# R3D2_v2.net
KiCad netlist of a schematic drawn in EAGLE
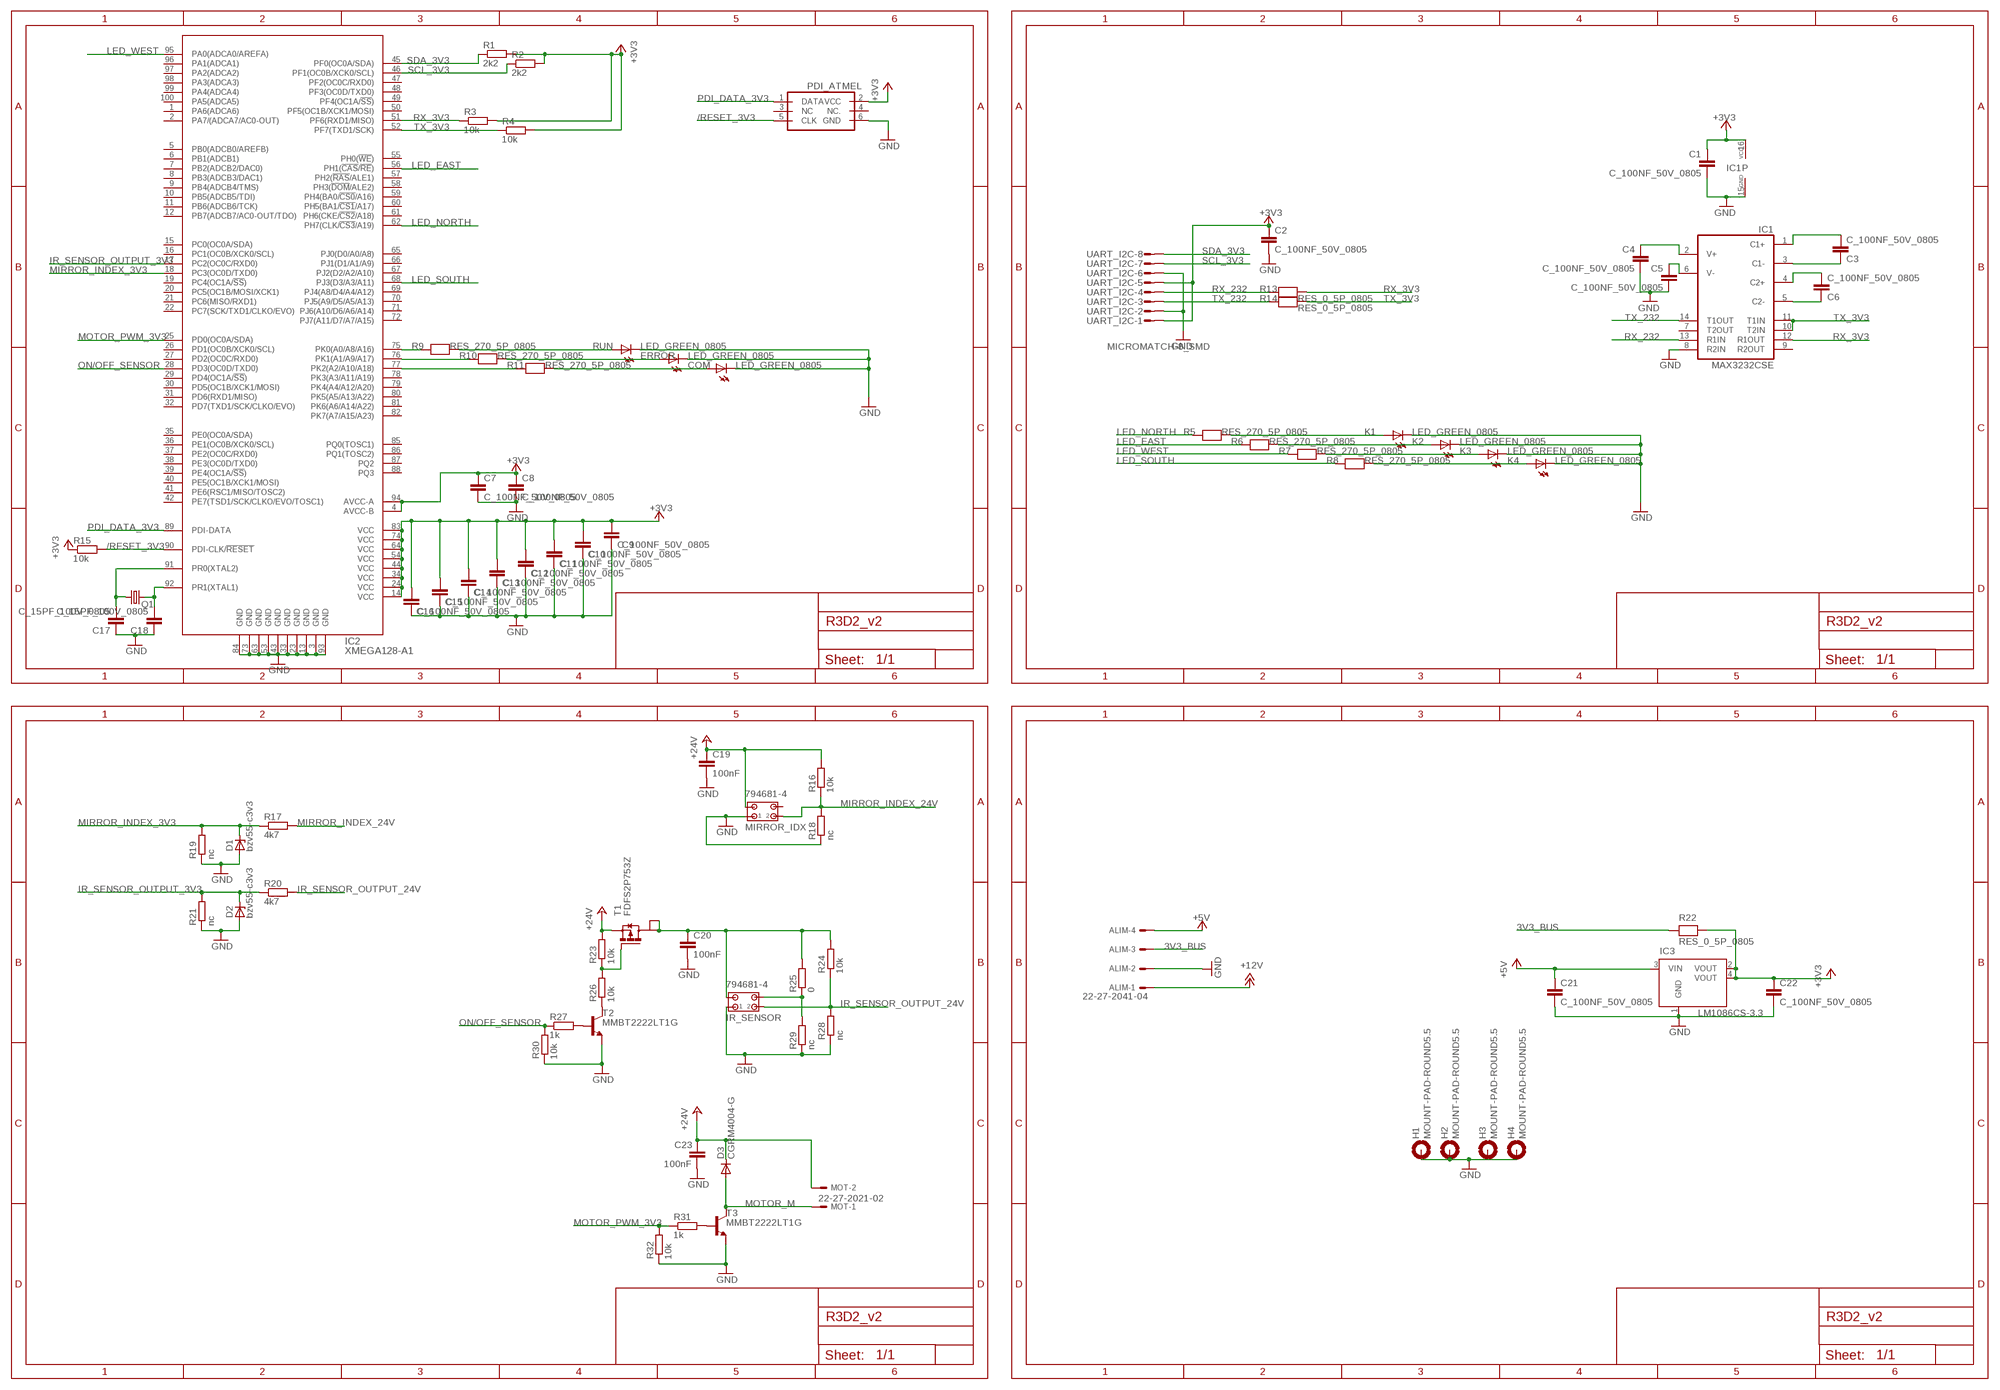
[diagram p0: schematic, sheet 1]

(export (version "E")
  (design (tool "Eeschema 10.0.6"))
  (components
    (comp (ref "ALIM")
      (value "22-27-2041-04")
      (footprint "eagle-import:6410-04")
      (libsource (lib "eagle-import") (part "22-?-0427-2041"))
    )
    (comp (ref "C1")
      (value "C_100NF_50V_0805")
      (footprint "eagle-import:C0805")
      (libsource (lib "eagle-import") (part "C_100NF_50V_0805"))
    )
    (comp (ref "C2")
      (value "C_100NF_50V_0805")
      (footprint "eagle-import:C0805")
      (libsource (lib "eagle-import") (part "C_100NF_50V_0805"))
    )
    (comp (ref "C3")
      (value "C_100NF_50V_0805")
      (footprint "eagle-import:C0805")
      (libsource (lib "eagle-import") (part "C_100NF_50V_0805"))
    )
    (comp (ref "C4")
      (value "C_100NF_50V_0805")
      (footprint "eagle-import:C0805")
      (libsource (lib "eagle-import") (part "C_100NF_50V_0805"))
    )
    (comp (ref "C5")
      (value "C_100NF_50V_0805")
      (footprint "eagle-import:C0805")
      (libsource (lib "eagle-import") (part "C_100NF_50V_0805"))
    )
    (comp (ref "C6")
      (value "C_100NF_50V_0805")
      (footprint "eagle-import:C0805")
      (libsource (lib "eagle-import") (part "C_100NF_50V_0805"))
    )
    (comp (ref "C7")
      (value "C_100NF_50V_0805")
      (footprint "eagle-import:C0805")
      (libsource (lib "eagle-import") (part "C_100NF_50V_0805"))
    )
    (comp (ref "C8")
      (value "C_100NF_50V_0805")
      (footprint "eagle-import:C0805")
      (libsource (lib "eagle-import") (part "C_100NF_50V_0805"))
    )
    (comp (ref "C9")
      (value "C_100NF_50V_0805")
      (footprint "eagle-import:C0805")
      (libsource (lib "eagle-import") (part "C_100NF_50V_0805"))
    )
    (comp (ref "C10")
      (value "C_100NF_50V_0805")
      (footprint "eagle-import:C0805")
      (libsource (lib "eagle-import") (part "C_100NF_50V_0805"))
    )
    (comp (ref "C11")
      (value "C_100NF_50V_0805")
      (footprint "eagle-import:C0805")
      (libsource (lib "eagle-import") (part "C_100NF_50V_0805"))
    )
    (comp (ref "C12")
      (value "C_100NF_50V_0805")
      (footprint "eagle-import:C0805")
      (libsource (lib "eagle-import") (part "C_100NF_50V_0805"))
    )
    (comp (ref "C13")
      (value "C_100NF_50V_0805")
      (footprint "eagle-import:C0805")
      (libsource (lib "eagle-import") (part "C_100NF_50V_0805"))
    )
    (comp (ref "C14")
      (value "C_100NF_50V_0805")
      (footprint "eagle-import:C0805")
      (libsource (lib "eagle-import") (part "C_100NF_50V_0805"))
    )
    (comp (ref "C15")
      (value "C_100NF_50V_0805")
      (footprint "eagle-import:C0805")
      (libsource (lib "eagle-import") (part "C_100NF_50V_0805"))
    )
    (comp (ref "C16")
      (value "C_100NF_50V_0805")
      (footprint "eagle-import:C0805")
      (libsource (lib "eagle-import") (part "C_100NF_50V_0805"))
    )
    (comp (ref "C17")
      (value "C_15PF_100V_0805")
      (footprint "eagle-import:C0805")
      (libsource (lib "eagle-import") (part "C_15PF_100V_0805"))
    )
    (comp (ref "C18")
      (value "C_15PF_100V_0805")
      (footprint "eagle-import:C0805")
      (libsource (lib "eagle-import") (part "C_15PF_100V_0805"))
    )
    (comp (ref "C19")
      (value "100nF")
      (footprint "eagle-import:C0805")
      (libsource (lib "eagle-import") (part "C-EUC0805"))
    )
    (comp (ref "C20")
      (value "100nF")
      (footprint "eagle-import:C0603")
      (libsource (lib "eagle-import") (part "C-EUC0603"))
    )
    (comp (ref "C21")
      (value "C_100NF_50V_0805")
      (footprint "eagle-import:C0805")
      (libsource (lib "eagle-import") (part "C_100NF_50V_0805"))
    )
    (comp (ref "C22")
      (value "C_100NF_50V_0805")
      (footprint "eagle-import:C0805")
      (libsource (lib "eagle-import") (part "C_100NF_50V_0805"))
    )
    (comp (ref "C23")
      (value "100nF")
      (footprint "eagle-import:C0805")
      (libsource (lib "eagle-import") (part "C-EUC0805"))
    )
    (comp (ref "COM")
      (value "LED_GREEN_0805")
      (footprint "eagle-import:CHIP-LED0805")
      (libsource (lib "eagle-import") (part "LED_GREEN_0805"))
    )
    (comp (ref "D1")
      (value "bzv55-c3v3")
      (footprint "eagle-import:SOD80C")
      (libsource (lib "eagle-import") (part "ZENER-DIODESOD80C"))
    )
    (comp (ref "D2")
      (value "bzv55-c3v3")
      (footprint "eagle-import:SOD80C")
      (libsource (lib "eagle-import") (part "ZENER-DIODESOD80C"))
    )
    (comp (ref "D3")
      (value "CGRM4004-G")
      (footprint "eagle-import:SOD-123_MINI-SMA")
      (libsource (lib "eagle-import") (part "CGRM400-G4"))
    )
    (comp (ref "ERROR")
      (value "LED_GREEN_0805")
      (footprint "eagle-import:CHIP-LED0805")
      (libsource (lib "eagle-import") (part "LED_GREEN_0805"))
    )
    (comp (ref "H1")
      (value "MOUNT-PAD-ROUND5.5")
      (footprint "eagle-import:5,5-PAD")
      (libsource (lib "eagle-import") (part "MOUNT-PAD-ROUND5.5"))
    )
    (comp (ref "H2")
      (value "MOUNT-PAD-ROUND5.5")
      (footprint "eagle-import:5,5-PAD")
      (libsource (lib "eagle-import") (part "MOUNT-PAD-ROUND5.5"))
    )
    (comp (ref "H3")
      (value "MOUNT-PAD-ROUND5.5")
      (footprint "eagle-import:5,5-PAD")
      (libsource (lib "eagle-import") (part "MOUNT-PAD-ROUND5.5"))
    )
    (comp (ref "H4")
      (value "MOUNT-PAD-ROUND5.5")
      (footprint "eagle-import:5,5-PAD")
      (libsource (lib "eagle-import") (part "MOUNT-PAD-ROUND5.5"))
    )
    (comp (ref "IC1")
      (value "MAX3232CSE")
      (footprint "eagle-import:SO16")
      (libsource (lib "eagle-import") (part "MAX3232SEC"))
    )
    (comp (ref "IC2")
      (value "XMEGA128-A1")
      (footprint "eagle-import:TQFP100")
      (libsource (lib "eagle-import") (part "XMEGA-A1TQFP"))
    )
    (comp (ref "IC3")
      (value "LM1086CS-3.3")
      (footprint "eagle-import:TO263")
      (libsource (lib "eagle-import") (part "LM1086CS-3.3"))
    )
    (comp (ref "IR_SENSOR")
      (value "794681-4")
      (footprint "eagle-import:794681-4")
      (libsource (lib "eagle-import") (part "794681-4"))
    )
    (comp (ref "K1")
      (value "LED_GREEN_0805")
      (footprint "eagle-import:CHIP-LED0805")
      (libsource (lib "eagle-import") (part "LED_GREEN_0805"))
    )
    (comp (ref "K2")
      (value "LED_GREEN_0805")
      (footprint "eagle-import:CHIP-LED0805")
      (libsource (lib "eagle-import") (part "LED_GREEN_0805"))
    )
    (comp (ref "K3")
      (value "LED_GREEN_0805")
      (footprint "eagle-import:CHIP-LED0805")
      (libsource (lib "eagle-import") (part "LED_GREEN_0805"))
    )
    (comp (ref "K4")
      (value "LED_GREEN_0805")
      (footprint "eagle-import:CHIP-LED0805")
      (libsource (lib "eagle-import") (part "LED_GREEN_0805"))
    )
    (comp (ref "MIRROR_IDX")
      (value "794681-4")
      (footprint "eagle-import:794681-4")
      (libsource (lib "eagle-import") (part "794681-4"))
    )
    (comp (ref "MOT")
      (value "22-27-2021-02")
      (footprint "eagle-import:6410-02")
      (libsource (lib "eagle-import") (part "22-?-0227-2021"))
    )
    (comp (ref "PDI_ATMEL")
      (value "PDI_ATMEL")
      (footprint "eagle-import:ML6")
      (libsource (lib "eagle-import") (part "PDI_ATMEL"))
    )
    (comp (ref "Q1")
      (value "CRYSTAL_16MHZ_HC49UP")
      (footprint "eagle-import:HC49UP")
      (libsource (lib "eagle-import") (part "CRYSTAL_16MHZ_HC49UP"))
    )
    (comp (ref "R1")
      (value "2k2")
      (footprint "eagle-import:R0603")
      (libsource (lib "eagle-import") (part "R-EU_R0603"))
    )
    (comp (ref "R2")
      (value "2k2")
      (footprint "eagle-import:R0603")
      (libsource (lib "eagle-import") (part "R-EU_R0603"))
    )
    (comp (ref "R3")
      (value "10k")
      (footprint "eagle-import:R0603")
      (libsource (lib "eagle-import") (part "R-EU_R0603"))
    )
    (comp (ref "R4")
      (value "10k")
      (footprint "eagle-import:R0603")
      (libsource (lib "eagle-import") (part "R-EU_R0603"))
    )
    (comp (ref "R5")
      (value "RES_270_5P_0805")
      (footprint "eagle-import:R0805")
      (libsource (lib "eagle-import") (part "RES_270_5P_0805"))
    )
    (comp (ref "R6")
      (value "RES_270_5P_0805")
      (footprint "eagle-import:R0805")
      (libsource (lib "eagle-import") (part "RES_270_5P_0805"))
    )
    (comp (ref "R7")
      (value "RES_270_5P_0805")
      (footprint "eagle-import:R0805")
      (libsource (lib "eagle-import") (part "RES_270_5P_0805"))
    )
    (comp (ref "R8")
      (value "RES_270_5P_0805")
      (footprint "eagle-import:R0805")
      (libsource (lib "eagle-import") (part "RES_270_5P_0805"))
    )
    (comp (ref "R9")
      (value "RES_270_5P_0805")
      (footprint "eagle-import:R0805")
      (libsource (lib "eagle-import") (part "RES_270_5P_0805"))
    )
    (comp (ref "R10")
      (value "RES_270_5P_0805")
      (footprint "eagle-import:R0805")
      (libsource (lib "eagle-import") (part "RES_270_5P_0805"))
    )
    (comp (ref "R11")
      (value "RES_270_5P_0805")
      (footprint "eagle-import:R0805")
      (libsource (lib "eagle-import") (part "RES_270_5P_0805"))
    )
    (comp (ref "R13")
      (value "RES_0_5P_0805")
      (footprint "eagle-import:R0805")
      (libsource (lib "eagle-import") (part "RES_0_5P_0805"))
    )
    (comp (ref "R14")
      (value "RES_0_5P_0805")
      (footprint "eagle-import:R0805")
      (libsource (lib "eagle-import") (part "RES_0_5P_0805"))
    )
    (comp (ref "R15")
      (value "10k")
      (footprint "eagle-import:R0603")
      (libsource (lib "eagle-import") (part "R-EU_R0603"))
    )
    (comp (ref "R16")
      (value "10k")
      (footprint "eagle-import:R0603")
      (libsource (lib "eagle-import") (part "R-EU_R0603"))
    )
    (comp (ref "R17")
      (value "4k7")
      (footprint "eagle-import:R0805")
      (libsource (lib "eagle-import") (part "R-EU_R0805"))
    )
    (comp (ref "R18")
      (value "nc")
      (footprint "eagle-import:R0805")
      (libsource (lib "eagle-import") (part "R-EU_R0805"))
    )
    (comp (ref "R19")
      (value "nc")
      (footprint "eagle-import:R0603")
      (libsource (lib "eagle-import") (part "R-EU_R0603"))
    )
    (comp (ref "R20")
      (value "4k7")
      (footprint "eagle-import:R0805")
      (libsource (lib "eagle-import") (part "R-EU_R0805"))
    )
    (comp (ref "R21")
      (value "nc")
      (footprint "eagle-import:R0603")
      (libsource (lib "eagle-import") (part "R-EU_R0603"))
    )
    (comp (ref "R22")
      (value "RES_0_5P_0805")
      (footprint "eagle-import:R0805")
      (libsource (lib "eagle-import") (part "RES_0_5P_0805"))
    )
    (comp (ref "R23")
      (value "10k")
      (footprint "eagle-import:R0603")
      (libsource (lib "eagle-import") (part "R-EU_R0603"))
    )
    (comp (ref "R24")
      (value "10k")
      (footprint "eagle-import:R0603")
      (libsource (lib "eagle-import") (part "R-EU_R0603"))
    )
    (comp (ref "R25")
      (value "0")
      (footprint "eagle-import:R0603")
      (libsource (lib "eagle-import") (part "R-EU_R0603"))
    )
    (comp (ref "R26")
      (value "10k")
      (footprint "eagle-import:R0603")
      (libsource (lib "eagle-import") (part "R-EU_R0603"))
    )
    (comp (ref "R27")
      (value "1k")
      (footprint "eagle-import:R0603")
      (libsource (lib "eagle-import") (part "R-EU_R0603"))
    )
    (comp (ref "R28")
      (value "nc")
      (footprint "eagle-import:R0603")
      (libsource (lib "eagle-import") (part "R-EU_R0603"))
    )
    (comp (ref "R29")
      (value "nc")
      (footprint "eagle-import:R0603")
      (libsource (lib "eagle-import") (part "R-EU_R0603"))
    )
    (comp (ref "R30")
      (value "10k")
      (footprint "eagle-import:R0603")
      (libsource (lib "eagle-import") (part "R-EU_R0603"))
    )
    (comp (ref "R31")
      (value "1k")
      (footprint "eagle-import:R0603")
      (libsource (lib "eagle-import") (part "R-EU_R0603"))
    )
    (comp (ref "R32")
      (value "10k")
      (footprint "eagle-import:R0603")
      (libsource (lib "eagle-import") (part "R-EU_R0603"))
    )
    (comp (ref "RUN")
      (value "LED_GREEN_0805")
      (footprint "eagle-import:CHIP-LED0805")
      (libsource (lib "eagle-import") (part "LED_GREEN_0805"))
    )
    (comp (ref "T1")
      (value "FDFS2P753Z")
      (footprint "eagle-import:SO8")
      (libsource (lib "eagle-import") (part "FDFS2P753Z"))
    )
    (comp (ref "T2")
      (value "MMBT2222LT1G")
      (footprint "eagle-import:SOT23-BEC")
      (libsource (lib "eagle-import") (part "-NPN-SOT23-BECMMBT2222ALT1"))
    )
    (comp (ref "T3")
      (value "MMBT2222LT1G")
      (footprint "eagle-import:SOT23-BEC")
      (libsource (lib "eagle-import") (part "-NPN-SOT23-BECMMBT2222ALT1"))
    )
    (comp (ref "UART_I2C")
      (value "MICROMATCH-8_SMD")
      (footprint "eagle-import:MICROMATCH-8_SMD")
      (libsource (lib "eagle-import") (part "MICROMATCH-8_SMD"))
    )
  )
  (nets
    (net (code "1") (name "+3V3") (class "Default")
      (node (ref "C1") (pin "1") (pinfunction "1_1") (pintype "passive"))
      (node (ref "C10") (pin "1") (pinfunction "1_1") (pintype "passive"))
      (node (ref "C11") (pin "1") (pinfunction "1_1") (pintype "passive"))
      (node (ref "C12") (pin "1") (pinfunction "1_1") (pintype "passive"))
      (node (ref "C13") (pin "1") (pinfunction "1_1") (pintype "passive"))
      (node (ref "C14") (pin "1") (pinfunction "1_1") (pintype "passive"))
      (node (ref "C15") (pin "1") (pinfunction "1_1") (pintype "passive"))
      (node (ref "C16") (pin "1") (pinfunction "1_1") (pintype "passive"))
      (node (ref "C2") (pin "1") (pinfunction "1_1") (pintype "passive"))
      (node (ref "C22") (pin "1") (pinfunction "1_1") (pintype "passive"))
      (node (ref "C7") (pin "1") (pinfunction "1_1") (pintype "passive"))
      (node (ref "C8") (pin "1") (pinfunction "1_1") (pintype "passive"))
      (node (ref "C9") (pin "1") (pinfunction "1_1") (pintype "passive"))
      (node (ref "IC1") (pin "16") (pinfunction "VCC_16") (pintype "power_in"))
      (node (ref "IC2") (pin "14") (pinfunction "VCC_14") (pintype "power_in"))
      (node (ref "IC2") (pin "24") (pinfunction "VCC_24") (pintype "power_in"))
      (node (ref "IC2") (pin "34") (pinfunction "VCC_34") (pintype "power_in"))
      (node (ref "IC2") (pin "4") (pinfunction "AVCC-B_4") (pintype "power_in"))
      (node (ref "IC2") (pin "44") (pinfunction "VCC_44") (pintype "power_in"))
      (node (ref "IC2") (pin "54") (pinfunction "VCC_54") (pintype "power_in"))
      (node (ref "IC2") (pin "64") (pinfunction "VCC_64") (pintype "power_in"))
      (node (ref "IC2") (pin "74") (pinfunction "VCC_74") (pintype "power_in"))
      (node (ref "IC2") (pin "83") (pinfunction "VCC_83") (pintype "power_in"))
      (node (ref "IC2") (pin "94") (pinfunction "AVCC-A_94") (pintype "power_in"))
      (node (ref "IC3") (pin "2") (pinfunction "VOUT_2") (pintype "bidirectional"))
      (node (ref "IC3") (pin "4") (pinfunction "VOUT_4") (pintype "bidirectional"))
      (node (ref "PDI_ATMEL") (pin "2") (pinfunction "VCC_2") (pintype "passive"))
      (node (ref "R1") (pin "2") (pinfunction "2_2") (pintype "passive"))
      (node (ref "R15") (pin "1") (pinfunction "1_1") (pintype "passive"))
      (node (ref "R2") (pin "2") (pinfunction "2_2") (pintype "passive"))
      (node (ref "R22") (pin "2") (pinfunction "2_2") (pintype "bidirectional"))
      (node (ref "R3") (pin "2") (pinfunction "2_2") (pintype "passive"))
      (node (ref "R4") (pin "2") (pinfunction "2_2") (pintype "passive"))
      (node (ref "UART_I2C") (pin "1") (pinfunction "S_1") (pintype "passive"))
      (node (ref "UART_I2C") (pin "5") (pinfunction "S_5") (pintype "passive"))
    )
    (net (code "2") (name "+5V") (class "Default")
      (node (ref "ALIM") (pin "4") (pinfunction "S_4") (pintype "passive"))
      (node (ref "C21") (pin "1") (pinfunction "1_1") (pintype "passive"))
      (node (ref "IC3") (pin "3") (pinfunction "VIN_3") (pintype "bidirectional"))
    )
    (net (code "3") (name "+12V") (class "Default")
      (node (ref "ALIM") (pin "1") (pinfunction "S_1") (pintype "passive"))
    )
    (net (code "4") (name "+24V") (class "Default")
      (node (ref "C19") (pin "1") (pinfunction "1_1") (pintype "passive"))
      (node (ref "C23") (pin "1") (pinfunction "1_1") (pintype "passive"))
      (node (ref "D3") (pin "C") (pinfunction "C_C") (pintype "passive"))
      (node (ref "MIRROR_IDX") (pin "3") (pinfunction "3_3") (pintype "passive"))
      (node (ref "MOT") (pin "2") (pinfunction "S_2") (pintype "passive"))
      (node (ref "R16") (pin "2") (pinfunction "2_2") (pintype "passive"))
      (node (ref "R23") (pin "2") (pinfunction "2_2") (pintype "passive"))
      (node (ref "T1") (pin "3") (pinfunction "S_3") (pintype "passive"))
    )
    (net (code "5") (name "/3V3_BUS") (class "Default")
      (node (ref "ALIM") (pin "3") (pinfunction "S_3") (pintype "passive"))
      (node (ref "R22") (pin "1") (pinfunction "1_1") (pintype "bidirectional"))
    )
    (net (code "6") (name "/IR_SENSOR_OUTPUT_3V3") (class "Default")
      (node (ref "D2") (pin "C") (pinfunction "C_C") (pintype "passive"))
      (node (ref "IC2") (pin "17") (pinfunction "PC2(OC0C/RXD0)_17") (pintype "bidirectional"))
      (node (ref "R20") (pin "1") (pinfunction "1_1") (pintype "passive"))
      (node (ref "R21") (pin "2") (pinfunction "2_2") (pintype "passive"))
    )
    (net (code "7") (name "/IR_SENSOR_OUTPUT_24V") (class "Default")
      (node (ref "IR_SENSOR") (pin "2") (pinfunction "2_2") (pintype "passive"))
      (node (ref "R20") (pin "2") (pinfunction "2_2") (pintype "passive"))
      (node (ref "R24") (pin "1") (pinfunction "1_1") (pintype "passive"))
      (node (ref "R28") (pin "2") (pinfunction "2_2") (pintype "passive"))
    )
    (net (code "8") (name "/LED_EAST") (class "Default")
      (node (ref "IC2") (pin "56") (pinfunction "PH1(~{CAS}/~{RE})_56") (pintype "bidirectional"))
      (node (ref "R6") (pin "1") (pinfunction "1_1") (pintype "bidirectional"))
    )
    (net (code "9") (name "/LED_NORTH") (class "Default")
      (node (ref "IC2") (pin "62") (pinfunction "PH7(CLK/~{CS3}/A19)_62") (pintype "bidirectional"))
      (node (ref "R5") (pin "1") (pinfunction "1_1") (pintype "bidirectional"))
    )
    (net (code "10") (name "/LED_SOUTH") (class "Default")
      (node (ref "IC2") (pin "68") (pinfunction "PJ3(D3/A3/A11)_68") (pintype "bidirectional"))
      (node (ref "R8") (pin "1") (pinfunction "1_1") (pintype "bidirectional"))
    )
    (net (code "11") (name "/LED_WEST") (class "Default")
      (node (ref "IC2") (pin "95") (pinfunction "PA0(ADCA0/AREFA)_95") (pintype "bidirectional"))
      (node (ref "R7") (pin "1") (pinfunction "1_1") (pintype "bidirectional"))
    )
    (net (code "12") (name "/MIRROR_INDEX_3V3") (class "Default")
      (node (ref "D1") (pin "C") (pinfunction "C_C") (pintype "passive"))
      (node (ref "IC2") (pin "18") (pinfunction "PC3(OC0D/TXD0)_18") (pintype "bidirectional"))
      (node (ref "R17") (pin "1") (pinfunction "1_1") (pintype "passive"))
      (node (ref "R19") (pin "2") (pinfunction "2_2") (pintype "passive"))
    )
    (net (code "13") (name "/MIRROR_INDEX_24V") (class "Default")
      (node (ref "MIRROR_IDX") (pin "2") (pinfunction "2_2") (pintype "passive"))
      (node (ref "R16") (pin "1") (pinfunction "1_1") (pintype "passive"))
      (node (ref "R17") (pin "2") (pinfunction "2_2") (pintype "passive"))
      (node (ref "R18") (pin "2") (pinfunction "2_2") (pintype "passive"))
    )
    (net (code "14") (name "/MOTOR_M") (class "Default")
      (node (ref "D3") (pin "A") (pinfunction "A_A") (pintype "passive"))
      (node (ref "MOT") (pin "1") (pinfunction "S_1") (pintype "passive"))
      (node (ref "T3") (pin "C") (pinfunction "C_C") (pintype "passive"))
    )
    (net (code "15") (name "/MOTOR_PWM_3V3") (class "Default")
      (node (ref "IC2") (pin "25") (pinfunction "PD0(OC0A/SDA)_25") (pintype "bidirectional"))
      (node (ref "R31") (pin "1") (pinfunction "1_1") (pintype "passive"))
      (node (ref "R32") (pin "2") (pinfunction "2_2") (pintype "passive"))
    )
    (net (code "16") (name "/ON{slash}OFF_SENSOR") (class "Default")
      (node (ref "IC2") (pin "28") (pinfunction "PD3(OC0D/TXD0)_28") (pintype "bidirectional"))
      (node (ref "R27") (pin "1") (pinfunction "1_1") (pintype "passive"))
      (node (ref "R30") (pin "2") (pinfunction "2_2") (pintype "passive"))
    )
    (net (code "17") (name "/PDI_DATA_3V3") (class "Default")
      (node (ref "IC2") (pin "89") (pinfunction "PDI-DATA_89") (pintype "bidirectional"))
      (node (ref "PDI_ATMEL") (pin "1") (pinfunction "DATA_1") (pintype "passive"))
    )
    (net (code "18") (name "/RX_3V3") (class "Default")
      (node (ref "IC1") (pin "12") (pinfunction "R1OUT_12") (pintype "output"))
      (node (ref "IC2") (pin "51") (pinfunction "PF6(RXD1/MISO)_51") (pintype "bidirectional"))
      (node (ref "R13") (pin "2") (pinfunction "2_2") (pintype "bidirectional"))
      (node (ref "R3") (pin "1") (pinfunction "1_1") (pintype "passive"))
    )
    (net (code "19") (name "/RX_232") (class "Default")
      (node (ref "IC1") (pin "13") (pinfunction "R1IN_13") (pintype "input"))
      (node (ref "R13") (pin "1") (pinfunction "1_1") (pintype "bidirectional"))
      (node (ref "UART_I2C") (pin "4") (pinfunction "S_4") (pintype "passive"))
    )
    (net (code "20") (name "/SCL_3V3") (class "Default")
      (node (ref "IC2") (pin "46") (pinfunction "PF1(OC0B/XCK0/SCL)_46") (pintype "bidirectional"))
      (node (ref "R2") (pin "1") (pinfunction "1_1") (pintype "passive"))
      (node (ref "UART_I2C") (pin "7") (pinfunction "S_7") (pintype "passive"))
    )
    (net (code "21") (name "/SDA_3V3") (class "Default")
      (node (ref "IC2") (pin "45") (pinfunction "PF0(OC0A/SDA)_45") (pintype "bidirectional"))
      (node (ref "R1") (pin "1") (pinfunction "1_1") (pintype "passive"))
      (node (ref "UART_I2C") (pin "8") (pinfunction "S_8") (pintype "passive"))
    )
    (net (code "22") (name "/TX_3V3") (class "Default")
      (node (ref "IC1") (pin "10") (pinfunction "T2IN_10") (pintype "input"))
      (node (ref "IC1") (pin "11") (pinfunction "T1IN_11") (pintype "input"))
      (node (ref "IC2") (pin "52") (pinfunction "PF7(TXD1/SCK)_52") (pintype "bidirectional"))
      (node (ref "R14") (pin "2") (pinfunction "2_2") (pintype "bidirectional"))
      (node (ref "R4") (pin "1") (pinfunction "1_1") (pintype "passive"))
    )
    (net (code "23") (name "/TX_232") (class "Default")
      (node (ref "IC1") (pin "14") (pinfunction "T1OUT_14") (pintype "output"))
      (node (ref "R14") (pin "1") (pinfunction "1_1") (pintype "bidirectional"))
      (node (ref "UART_I2C") (pin "3") (pinfunction "S_3") (pintype "passive"))
    )
    (net (code "24") (name "/{slash}RESET_3V3") (class "Default")
      (node (ref "IC2") (pin "90") (pinfunction "PDI-CLK/~{RESET}_90") (pintype "input"))
      (node (ref "PDI_ATMEL") (pin "5") (pinfunction "CLK_5") (pintype "passive"))
      (node (ref "R15") (pin "2") (pinfunction "2_2") (pintype "passive"))
    )
    (net (code "25") (name "GND") (class "Default")
      (node (ref "ALIM") (pin "2") (pinfunction "S_2") (pintype "passive"))
      (node (ref "C1") (pin "2") (pinfunction "2_2") (pintype "passive"))
      (node (ref "C10") (pin "2") (pinfunction "2_2") (pintype "passive"))
      (node (ref "C11") (pin "2") (pinfunction "2_2") (pintype "passive"))
      (node (ref "C12") (pin "2") (pinfunction "2_2") (pintype "passive"))
      (node (ref "C13") (pin "2") (pinfunction "2_2") (pintype "passive"))
      (node (ref "C14") (pin "2") (pinfunction "2_2") (pintype "passive"))
      (node (ref "C15") (pin "2") (pinfunction "2_2") (pintype "passive"))
      (node (ref "C16") (pin "2") (pinfunction "2_2") (pintype "passive"))
      (node (ref "C17") (pin "1") (pinfunction "1_1") (pintype "passive"))
      (node (ref "C18") (pin "1") (pinfunction "1_1") (pintype "passive"))
      (node (ref "C19") (pin "2") (pinfunction "2_2") (pintype "passive"))
      (node (ref "C2") (pin "2") (pinfunction "2_2") (pintype "passive"))
      (node (ref "C20") (pin "2") (pinfunction "2_2") (pintype "passive"))
      (node (ref "C21") (pin "2") (pinfunction "2_2") (pintype "passive"))
      (node (ref "C22") (pin "2") (pinfunction "2_2") (pintype "passive"))
      (node (ref "C23") (pin "2") (pinfunction "2_2") (pintype "passive"))
      (node (ref "C4") (pin "2") (pinfunction "2_2") (pintype "passive"))
      (node (ref "C5") (pin "2") (pinfunction "2_2") (pintype "passive"))
      (node (ref "C7") (pin "2") (pinfunction "2_2") (pintype "passive"))
      (node (ref "C8") (pin "2") (pinfunction "2_2") (pintype "passive"))
      (node (ref "C9") (pin "2") (pinfunction "2_2") (pintype "passive"))
      (node (ref "COM") (pin "C") (pinfunction "C_C") (pintype "passive"))
      (node (ref "D1") (pin "A") (pinfunction "A_A") (pintype "passive"))
      (node (ref "D2") (pin "A") (pinfunction "A_A") (pintype "passive"))
      (node (ref "ERROR") (pin "C") (pinfunction "C_C") (pintype "passive"))
      (node (ref "H1") (pin "B5,5") (pinfunction "MOUNT_B5,5") (pintype "passive"))
      (node (ref "H2") (pin "B5,5") (pinfunction "MOUNT_B5,5") (pintype "passive"))
      (node (ref "H3") (pin "B5,5") (pinfunction "MOUNT_B5,5") (pintype "passive"))
      (node (ref "H4") (pin "B5,5") (pinfunction "MOUNT_B5,5") (pintype "passive"))
      (node (ref "IC1") (pin "15") (pinfunction "GND_15") (pintype "power_in"))
      (node (ref "IC1") (pin "8") (pinfunction "R2IN_8") (pintype "input"))
      (node (ref "IC2") (pin "13") (pinfunction "GND_13") (pintype "power_in"))
      (node (ref "IC2") (pin "23") (pinfunction "GND_23") (pintype "power_in"))
      (node (ref "IC2") (pin "3") (pinfunction "GND_3") (pintype "power_in"))
      (node (ref "IC2") (pin "33") (pinfunction "GND_33") (pintype "power_in"))
      (node (ref "IC2") (pin "43") (pinfunction "GND_43") (pintype "power_in"))
      (node (ref "IC2") (pin "53") (pinfunction "GND_53") (pintype "power_in"))
      (node (ref "IC2") (pin "63") (pinfunction "GND_63") (pintype "power_in"))
      (node (ref "IC2") (pin "73") (pinfunction "GND_73") (pintype "power_in"))
      (node (ref "IC2") (pin "84") (pinfunction "GND_84") (pintype "power_in"))
      (node (ref "IC2") (pin "93") (pinfunction "GND_93") (pintype "power_in"))
      (node (ref "IC3") (pin "1") (pinfunction "GND_1") (pintype "bidirectional"))
      (node (ref "IR_SENSOR") (pin "1") (pinfunction "1_1") (pintype "passive"))
      (node (ref "K1") (pin "C") (pinfunction "C_C") (pintype "passive"))
      (node (ref "K2") (pin "C") (pinfunction "C_C") (pintype "passive"))
      (node (ref "K3") (pin "C") (pinfunction "C_C") (pintype "passive"))
      (node (ref "K4") (pin "C") (pinfunction "C_C") (pintype "passive"))
      (node (ref "MIRROR_IDX") (pin "1") (pinfunction "1_1") (pintype "passive"))
      (node (ref "PDI_ATMEL") (pin "6") (pinfunction "GND_6") (pintype "passive"))
      (node (ref "R18") (pin "1") (pinfunction "1_1") (pintype "passive"))
      (node (ref "R19") (pin "1") (pinfunction "1_1") (pintype "passive"))
      (node (ref "R21") (pin "1") (pinfunction "1_1") (pintype "passive"))
      (node (ref "R28") (pin "1") (pinfunction "1_1") (pintype "passive"))
      (node (ref "R29") (pin "1") (pinfunction "1_1") (pintype "passive"))
      (node (ref "R30") (pin "1") (pinfunction "1_1") (pintype "passive"))
      (node (ref "R32") (pin "1") (pinfunction "1_1") (pintype "passive"))
      (node (ref "RUN") (pin "C") (pinfunction "C_C") (pintype "passive"))
      (node (ref "T2") (pin "E") (pinfunction "E_E") (pintype "passive"))
      (node (ref "T3") (pin "E") (pinfunction "E_E") (pintype "passive"))
      (node (ref "UART_I2C") (pin "2") (pinfunction "S_2") (pintype "passive"))
      (node (ref "UART_I2C") (pin "6") (pinfunction "S_6") (pintype "passive"))
    )
    (net (code "26") (name "Net-(COM-PadA)") (class "Default")
      (node (ref "COM") (pin "A") (pinfunction "A_A") (pintype "passive"))
      (node (ref "R11") (pin "2") (pinfunction "2_2") (pintype "bidirectional"))
    )
    (net (code "27") (name "Net-(ERROR-PadA)") (class "Default")
      (node (ref "ERROR") (pin "A") (pinfunction "A_A") (pintype "passive"))
      (node (ref "R10") (pin "2") (pinfunction "2_2") (pintype "bidirectional"))
    )
    (net (code "28") (name "Net-(IC1A-C1+)") (class "Default")
      (node (ref "C3") (pin "1") (pinfunction "1_1") (pintype "passive"))
      (node (ref "IC1") (pin "1") (pinfunction "C1+_1") (pintype "bidirectional"))
    )
    (net (code "29") (name "Net-(IC1A-C1-)") (class "Default")
      (node (ref "C3") (pin "2") (pinfunction "2_2") (pintype "passive"))
      (node (ref "IC1") (pin "3") (pinfunction "C1-_3") (pintype "bidirectional"))
    )
    (net (code "30") (name "Net-(IC1A-C2+)") (class "Default")
      (node (ref "C6") (pin "1") (pinfunction "1_1") (pintype "passive"))
      (node (ref "IC1") (pin "4") (pinfunction "C2+_4") (pintype "bidirectional"))
    )
    (net (code "31") (name "Net-(IC1A-C2-)") (class "Default")
      (node (ref "C6") (pin "2") (pinfunction "2_2") (pintype "passive"))
      (node (ref "IC1") (pin "5") (pinfunction "C2-_5") (pintype "bidirectional"))
    )
    (net (code "32") (name "Net-(IC1A-V+)") (class "Default")
      (node (ref "C4") (pin "1") (pinfunction "1_1") (pintype "passive"))
      (node (ref "IC1") (pin "2") (pinfunction "V+_2") (pintype "bidirectional"))
    )
    (net (code "33") (name "Net-(IC1A-V-)") (class "Default")
      (node (ref "C5") (pin "1") (pinfunction "1_1") (pintype "passive"))
      (node (ref "IC1") (pin "6") (pinfunction "V-_6") (pintype "bidirectional"))
    )
    (net (code "34") (name "Net-(IC2-PK0(A0{slash}A8{slash}A16))") (class "Default")
      (node (ref "IC2") (pin "75") (pinfunction "PK0(A0/A8/A16)_75") (pintype "bidirectional"))
      (node (ref "R9") (pin "1") (pinfunction "1_1") (pintype "bidirectional"))
    )
    (net (code "35") (name "Net-(IC2-PK1(A1{slash}A9{slash}A17))") (class "Default")
      (node (ref "IC2") (pin "76") (pinfunction "PK1(A1/A9/A17)_76") (pintype "bidirectional"))
      (node (ref "R10") (pin "1") (pinfunction "1_1") (pintype "bidirectional"))
    )
    (net (code "36") (name "Net-(IC2-PK2(A2{slash}A10{slash}A18))") (class "Default")
      (node (ref "IC2") (pin "77") (pinfunction "PK2(A2/A10/A18)_77") (pintype "bidirectional"))
      (node (ref "R11") (pin "1") (pinfunction "1_1") (pintype "bidirectional"))
    )
    (net (code "37") (name "Net-(IC2-PR0(XTAL2))") (class "Default")
      (node (ref "C17") (pin "2") (pinfunction "2_2") (pintype "passive"))
      (node (ref "IC2") (pin "91") (pinfunction "PR0(XTAL2)_91") (pintype "bidirectional"))
      (node (ref "Q1") (pin "1") (pinfunction "1_1") (pintype "passive"))
    )
    (net (code "38") (name "Net-(IC2-PR1(XTAL1))") (class "Default")
      (node (ref "C18") (pin "2") (pinfunction "2_2") (pintype "passive"))
      (node (ref "IC2") (pin "92") (pinfunction "PR1(XTAL1)_92") (pintype "bidirectional"))
      (node (ref "Q1") (pin "2") (pinfunction "2_2") (pintype "passive"))
    )
    (net (code "39") (name "Net-(IR_SENSOR-Pad4)") (class "Default")
      (node (ref "IR_SENSOR") (pin "4") (pinfunction "4_4") (pintype "passive"))
      (node (ref "R25") (pin "1") (pinfunction "1_1") (pintype "passive"))
      (node (ref "R29") (pin "2") (pinfunction "2_2") (pintype "passive"))
    )
    (net (code "40") (name "Net-(K1-PadA)") (class "Default")
      (node (ref "K1") (pin "A") (pinfunction "A_A") (pintype "passive"))
      (node (ref "R5") (pin "2") (pinfunction "2_2") (pintype "bidirectional"))
    )
    (net (code "41") (name "Net-(K2-PadA)") (class "Default")
      (node (ref "K2") (pin "A") (pinfunction "A_A") (pintype "passive"))
      (node (ref "R6") (pin "2") (pinfunction "2_2") (pintype "bidirectional"))
    )
    (net (code "42") (name "Net-(K3-PadA)") (class "Default")
      (node (ref "K3") (pin "A") (pinfunction "A_A") (pintype "passive"))
      (node (ref "R7") (pin "2") (pinfunction "2_2") (pintype "bidirectional"))
    )
    (net (code "43") (name "Net-(K4-PadA)") (class "Default")
      (node (ref "K4") (pin "A") (pinfunction "A_A") (pintype "passive"))
      (node (ref "R8") (pin "2") (pinfunction "2_2") (pintype "bidirectional"))
    )
    (net (code "44") (name "Net-(R9-Pad2)") (class "Default")
      (node (ref "R9") (pin "2") (pinfunction "2_2") (pintype "bidirectional"))
      (node (ref "RUN") (pin "A") (pinfunction "A_A") (pintype "passive"))
    )
    (net (code "45") (name "Net-(R26-Pad1)") (class "Default")
      (node (ref "R26") (pin "1") (pinfunction "1_1") (pintype "passive"))
      (node (ref "T2") (pin "C") (pinfunction "C_C") (pintype "passive"))
    )
    (net (code "46") (name "Net-(R27-Pad2)") (class "Default")
      (node (ref "R27") (pin "2") (pinfunction "2_2") (pintype "passive"))
      (node (ref "T2") (pin "B") (pinfunction "B_B") (pintype "passive"))
    )
    (net (code "47") (name "Net-(R31-Pad2)") (class "Default")
      (node (ref "R31") (pin "2") (pinfunction "2_2") (pintype "passive"))
      (node (ref "T3") (pin "B") (pinfunction "B_B") (pintype "passive"))
    )
    (net (code "48") (name "Net-(T1-D)") (class "Default")
      (node (ref "C20") (pin "1") (pinfunction "1_1") (pintype "passive"))
      (node (ref "IR_SENSOR") (pin "3") (pinfunction "3_3") (pintype "passive"))
      (node (ref "R24") (pin "2") (pinfunction "2_2") (pintype "passive"))
      (node (ref "R25") (pin "2") (pinfunction "2_2") (pintype "passive"))
      (node (ref "T1") (pin "5") (pinfunction "D_5") (pintype "passive"))
      (node (ref "T1") (pin "6") (pinfunction "D1_6") (pintype "passive"))
    )
    (net (code "49") (name "Net-(T1-G)") (class "Default")
      (node (ref "R23") (pin "1") (pinfunction "1_1") (pintype "passive"))
      (node (ref "R26") (pin "2") (pinfunction "2_2") (pintype "passive"))
      (node (ref "T1") (pin "4") (pinfunction "G_4") (pintype "passive"))
    )
    (net (code "50") (name "unconnected-(IC1A-R2OUT-Pad9)") (class "Default")
      (node (ref "IC1") (pin "9") (pinfunction "R2OUT_9") (pintype "output"))
    )
    (net (code "51") (name "unconnected-(IC1A-T2OUT-Pad7)") (class "Default")
      (node (ref "IC1") (pin "7") (pinfunction "T2OUT_7") (pintype "output"))
    )
    (net (code "52") (name "unconnected-(IC2-PA1(ADCA1)-Pad96)") (class "Default")
      (node (ref "IC2") (pin "96") (pinfunction "PA1(ADCA1)_96") (pintype "bidirectional"))
    )
    (net (code "53") (name "unconnected-(IC2-PA2(ADCA2)-Pad97)") (class "Default")
      (node (ref "IC2") (pin "97") (pinfunction "PA2(ADCA2)_97") (pintype "bidirectional"))
    )
    (net (code "54") (name "unconnected-(IC2-PA3(ADCA3)-Pad98)") (class "Default")
      (node (ref "IC2") (pin "98") (pinfunction "PA3(ADCA3)_98") (pintype "bidirectional"))
    )
    (net (code "55") (name "unconnected-(IC2-PA4(ADCA4)-Pad99)") (class "Default")
      (node (ref "IC2") (pin "99") (pinfunction "PA4(ADCA4)_99") (pintype "bidirectional"))
    )
    (net (code "56") (name "unconnected-(IC2-PA5(ADCA5)-Pad100)") (class "Default")
      (node (ref "IC2") (pin "100") (pinfunction "PA5(ADCA5)_100") (pintype "bidirectional"))
    )
    (net (code "57") (name "unconnected-(IC2-PA6(ADCA6)-Pad1)") (class "Default")
      (node (ref "IC2") (pin "1") (pinfunction "PA6(ADCA6)_1") (pintype "bidirectional"))
    )
    (net (code "58") (name "unconnected-(IC2-PA7{slash}(ADCA7{slash}AC0-OUT)-Pad2)") (class "Default")
      (node (ref "IC2") (pin "2") (pinfunction "PA7/(ADCA7/AC0-OUT)_2") (pintype "bidirectional"))
    )
    (net (code "59") (name "unconnected-(IC2-PB0(ADCB0{slash}AREFB)-Pad5)") (class "Default")
      (node (ref "IC2") (pin "5") (pinfunction "PB0(ADCB0/AREFB)_5") (pintype "bidirectional"))
    )
    (net (code "60") (name "unconnected-(IC2-PB1(ADCB1)-Pad6)") (class "Default")
      (node (ref "IC2") (pin "6") (pinfunction "PB1(ADCB1)_6") (pintype "bidirectional"))
    )
    (net (code "61") (name "unconnected-(IC2-PB2(ADCB2{slash}DAC0)-Pad7)") (class "Default")
      (node (ref "IC2") (pin "7") (pinfunction "PB2(ADCB2/DAC0)_7") (pintype "bidirectional"))
    )
    (net (code "62") (name "unconnected-(IC2-PB3(ADCB3{slash}DAC1)-Pad8)") (class "Default")
      (node (ref "IC2") (pin "8") (pinfunction "PB3(ADCB3/DAC1)_8") (pintype "bidirectional"))
    )
    (net (code "63") (name "unconnected-(IC2-PB4(ADCB4{slash}TMS)-Pad9)") (class "Default")
      (node (ref "IC2") (pin "9") (pinfunction "PB4(ADCB4/TMS)_9") (pintype "bidirectional"))
    )
    (net (code "64") (name "unconnected-(IC2-PB5(ADCB5{slash}TDI)-Pad10)") (class "Default")
      (node (ref "IC2") (pin "10") (pinfunction "PB5(ADCB5/TDI)_10") (pintype "bidirectional"))
    )
    (net (code "65") (name "unconnected-(IC2-PB6(ADCB6{slash}TCK)-Pad11)") (class "Default")
      (node (ref "IC2") (pin "11") (pinfunction "PB6(ADCB6/TCK)_11") (pintype "bidirectional"))
    )
    (net (code "66") (name "unconnected-(IC2-PB7(ADCB7{slash}AC0-OUT{slash}TDO)-Pad12)") (class "Default")
      (node (ref "IC2") (pin "12") (pinfunction "PB7(ADCB7/AC0-OUT/TDO)_12") (pintype "bidirectional"))
    )
    (net (code "67") (name "unconnected-(IC2-PC0(OC0A{slash}SDA)-Pad15)") (class "Default")
      (node (ref "IC2") (pin "15") (pinfunction "PC0(OC0A/SDA)_15") (pintype "bidirectional"))
    )
    (net (code "68") (name "unconnected-(IC2-PC1(OC0B{slash}XCK0{slash}SCL)-Pad16)") (class "Default")
      (node (ref "IC2") (pin "16") (pinfunction "PC1(OC0B/XCK0/SCL)_16") (pintype "bidirectional"))
    )
    (net (code "69") (name "unconnected-(IC2-PC4(OC1A{slash}~{SS})-Pad19)") (class "Default")
      (node (ref "IC2") (pin "19") (pinfunction "PC4(OC1A/~{SS})_19") (pintype "bidirectional"))
    )
    (net (code "70") (name "unconnected-(IC2-PC5(OC1B{slash}MOSI{slash}XCK1)-Pad20)") (class "Default")
      (node (ref "IC2") (pin "20") (pinfunction "PC5(OC1B/MOSI/XCK1)_20") (pintype "bidirectional"))
    )
    (net (code "71") (name "unconnected-(IC2-PC6(MISO{slash}RXD1)-Pad21)") (class "Default")
      (node (ref "IC2") (pin "21") (pinfunction "PC6(MISO/RXD1)_21") (pintype "bidirectional"))
    )
    (net (code "72") (name "unconnected-(IC2-PC7(SCK{slash}TXD1{slash}CLKO{slash}EVO)-Pad22)") (class "Default")
      (node (ref "IC2") (pin "22") (pinfunction "PC7(SCK/TXD1/CLKO/EVO)_22") (pintype "bidirectional"))
    )
    (net (code "73") (name "unconnected-(IC2-PD1(OC0B{slash}XCK0{slash}SCL)-Pad26)") (class "Default")
      (node (ref "IC2") (pin "26") (pinfunction "PD1(OC0B/XCK0/SCL)_26") (pintype "bidirectional"))
    )
    (net (code "74") (name "unconnected-(IC2-PD2(OC0C{slash}RXD0)-Pad27)") (class "Default")
      (node (ref "IC2") (pin "27") (pinfunction "PD2(OC0C/RXD0)_27") (pintype "bidirectional"))
    )
    (net (code "75") (name "unconnected-(IC2-PD4(OC1A{slash}~{SS})-Pad29)") (class "Default")
      (node (ref "IC2") (pin "29") (pinfunction "PD4(OC1A/~{SS})_29") (pintype "bidirectional"))
    )
    (net (code "76") (name "unconnected-(IC2-PD5(OC1B{slash}XCK1{slash}MOSI)-Pad30)") (class "Default")
      (node (ref "IC2") (pin "30") (pinfunction "PD5(OC1B/XCK1/MOSI)_30") (pintype "bidirectional"))
    )
    (net (code "77") (name "unconnected-(IC2-PD6(RXD1{slash}MISO)-Pad31)") (class "Default")
      (node (ref "IC2") (pin "31") (pinfunction "PD6(RXD1/MISO)_31") (pintype "bidirectional"))
    )
    (net (code "78") (name "unconnected-(IC2-PD7(TXD1{slash}SCK{slash}CLKO{slash}EVO)-Pad32)") (class "Default")
      (node (ref "IC2") (pin "32") (pinfunction "PD7(TXD1/SCK/CLKO/EVO)_32") (pintype "bidirectional"))
    )
    (net (code "79") (name "unconnected-(IC2-PE0(OC0A{slash}SDA)-Pad35)") (class "Default")
      (node (ref "IC2") (pin "35") (pinfunction "PE0(OC0A/SDA)_35") (pintype "bidirectional"))
    )
    (net (code "80") (name "unconnected-(IC2-PE1(OC0B{slash}XCK0{slash}SCL)-Pad36)") (class "Default")
      (node (ref "IC2") (pin "36") (pinfunction "PE1(OC0B/XCK0/SCL)_36") (pintype "bidirectional"))
    )
    (net (code "81") (name "unconnected-(IC2-PE2(OC0C{slash}RXD0)-Pad37)") (class "Default")
      (node (ref "IC2") (pin "37") (pinfunction "PE2(OC0C/RXD0)_37") (pintype "bidirectional"))
    )
    (net (code "82") (name "unconnected-(IC2-PE3(OC0D{slash}TXD0)-Pad38)") (class "Default")
      (node (ref "IC2") (pin "38") (pinfunction "PE3(OC0D/TXD0)_38") (pintype "bidirectional"))
    )
    (net (code "83") (name "unconnected-(IC2-PE4(OC1A{slash}~{SS})-Pad39)") (class "Default")
      (node (ref "IC2") (pin "39") (pinfunction "PE4(OC1A/~{SS})_39") (pintype "bidirectional"))
    )
    (net (code "84") (name "unconnected-(IC2-PE5(OC1B{slash}XCK1{slash}MOSI)-Pad40)") (class "Default")
      (node (ref "IC2") (pin "40") (pinfunction "PE5(OC1B/XCK1/MOSI)_40") (pintype "bidirectional"))
    )
    (net (code "85") (name "unconnected-(IC2-PE6(RSC1{slash}MISO{slash}TOSC2)-Pad41)") (class "Default")
      (node (ref "IC2") (pin "41") (pinfunction "PE6(RSC1/MISO/TOSC2)_41") (pintype "bidirectional"))
    )
    (net (code "86") (name "unconnected-(IC2-PE7(TSD1{slash}SCK{slash}CLKO{slash}EVO{slash}TOSC1)-Pad42)") (class "Default")
      (node (ref "IC2") (pin "42") (pinfunction "PE7(TSD1/SCK/CLKO/EVO/TOSC1)_42") (pintype "bidirectional"))
    )
    (net (code "87") (name "unconnected-(IC2-PF2(OC0C{slash}RXD0)-Pad47)") (class "Default")
      (node (ref "IC2") (pin "47") (pinfunction "PF2(OC0C/RXD0)_47") (pintype "bidirectional"))
    )
    (net (code "88") (name "unconnected-(IC2-PF3(OC0D{slash}TXD0)-Pad48)") (class "Default")
      (node (ref "IC2") (pin "48") (pinfunction "PF3(OC0D/TXD0)_48") (pintype "bidirectional"))
    )
    (net (code "89") (name "unconnected-(IC2-PF4(OC1A{slash}~{SS})-Pad49)") (class "Default")
      (node (ref "IC2") (pin "49") (pinfunction "PF4(OC1A/~{SS})_49") (pintype "bidirectional"))
    )
    (net (code "90") (name "unconnected-(IC2-PF5(OC1B{slash}XCK1{slash}MOSI)-Pad50)") (class "Default")
      (node (ref "IC2") (pin "50") (pinfunction "PF5(OC1B/XCK1/MOSI)_50") (pintype "bidirectional"))
    )
    (net (code "91") (name "unconnected-(IC2-PH0(~{WE})-Pad55)") (class "Default")
      (node (ref "IC2") (pin "55") (pinfunction "PH0(~{WE})_55") (pintype "bidirectional"))
    )
    (net (code "92") (name "unconnected-(IC2-PH2(~{RAS}{slash}ALE1)-Pad57)") (class "Default")
      (node (ref "IC2") (pin "57") (pinfunction "PH2(~{RAS}/ALE1)_57") (pintype "bidirectional"))
    )
    (net (code "93") (name "unconnected-(IC2-PH3(~{DOM}{slash}ALE2)-Pad58)") (class "Default")
      (node (ref "IC2") (pin "58") (pinfunction "PH3(~{DOM}/ALE2)_58") (pintype "bidirectional"))
    )
    (net (code "94") (name "unconnected-(IC2-PH4(BA0{slash}~{CS0}{slash}A16)-Pad59)") (class "Default")
      (node (ref "IC2") (pin "59") (pinfunction "PH4(BA0/~{CS0}/A16)_59") (pintype "bidirectional"))
    )
    (net (code "95") (name "unconnected-(IC2-PH5(BA1{slash}~{CS1}{slash}A17)-Pad60)") (class "Default")
      (node (ref "IC2") (pin "60") (pinfunction "PH5(BA1/~{CS1}/A17)_60") (pintype "bidirectional"))
    )
    (net (code "96") (name "unconnected-(IC2-PH6(CKE{slash}~{CS2}{slash}A18)-Pad61)") (class "Default")
      (node (ref "IC2") (pin "61") (pinfunction "PH6(CKE/~{CS2}/A18)_61") (pintype "bidirectional"))
    )
    (net (code "97") (name "unconnected-(IC2-PJ0(D0{slash}A0{slash}A8)-Pad65)") (class "Default")
      (node (ref "IC2") (pin "65") (pinfunction "PJ0(D0/A0/A8)_65") (pintype "bidirectional"))
    )
    (net (code "98") (name "unconnected-(IC2-PJ1(D1{slash}A1{slash}A9)-Pad66)") (class "Default")
      (node (ref "IC2") (pin "66") (pinfunction "PJ1(D1/A1/A9)_66") (pintype "bidirectional"))
    )
    (net (code "99") (name "unconnected-(IC2-PJ2(D2{slash}A2{slash}A10)-Pad67)") (class "Default")
      (node (ref "IC2") (pin "67") (pinfunction "PJ2(D2/A2/A10)_67") (pintype "bidirectional"))
    )
    (net (code "100") (name "unconnected-(IC2-PJ4(A8{slash}D4{slash}A4{slash}A12)-Pad69)") (class "Default")
      (node (ref "IC2") (pin "69") (pinfunction "PJ4(A8/D4/A4/A12)_69") (pintype "bidirectional"))
    )
    (net (code "101") (name "unconnected-(IC2-PJ5(A9{slash}D5{slash}A5{slash}A13)-Pad70)") (class "Default")
      (node (ref "IC2") (pin "70") (pinfunction "PJ5(A9/D5/A5/A13)_70") (pintype "bidirectional"))
    )
    (net (code "102") (name "unconnected-(IC2-PJ6(A10{slash}D6{slash}A6{slash}A14)-Pad71)") (class "Default")
      (node (ref "IC2") (pin "71") (pinfunction "PJ6(A10/D6/A6/A14)_71") (pintype "bidirectional"))
    )
    (net (code "103") (name "unconnected-(IC2-PJ7(A11{slash}D7{slash}A7{slash}A15)-Pad72)") (class "Default")
      (node (ref "IC2") (pin "72") (pinfunction "PJ7(A11/D7/A7/A15)_72") (pintype "bidirectional"))
    )
    (net (code "104") (name "unconnected-(IC2-PK3(A3{slash}A11{slash}A19)-Pad78)") (class "Default")
      (node (ref "IC2") (pin "78") (pinfunction "PK3(A3/A11/A19)_78") (pintype "bidirectional"))
    )
    (net (code "105") (name "unconnected-(IC2-PK4(A4{slash}A12{slash}A20)-Pad79)") (class "Default")
      (node (ref "IC2") (pin "79") (pinfunction "PK4(A4/A12/A20)_79") (pintype "bidirectional"))
    )
    (net (code "106") (name "unconnected-(IC2-PK5(A5{slash}A13{slash}A22)-Pad80)") (class "Default")
      (node (ref "IC2") (pin "80") (pinfunction "PK5(A5/A13/A22)_80") (pintype "bidirectional"))
    )
    (net (code "107") (name "unconnected-(IC2-PK6(A6{slash}A14{slash}A22)-Pad81)") (class "Default")
      (node (ref "IC2") (pin "81") (pinfunction "PK6(A6/A14/A22)_81") (pintype "bidirectional"))
    )
    (net (code "108") (name "unconnected-(IC2-PK7(A7{slash}A15{slash}A23)-Pad82)") (class "Default")
      (node (ref "IC2") (pin "82") (pinfunction "PK7(A7/A15/A23)_82") (pintype "bidirectional"))
    )
    (net (code "109") (name "unconnected-(IC2-PQ0(TOSC1)-Pad85)") (class "Default")
      (node (ref "IC2") (pin "85") (pinfunction "PQ0(TOSC1)_85") (pintype "bidirectional"))
    )
    (net (code "110") (name "unconnected-(IC2-PQ1(TOSC2)-Pad86)") (class "Default")
      (node (ref "IC2") (pin "86") (pinfunction "PQ1(TOSC2)_86") (pintype "bidirectional"))
    )
    (net (code "111") (name "unconnected-(IC2-PQ2-Pad87)") (class "Default")
      (node (ref "IC2") (pin "87") (pinfunction "PQ2_87") (pintype "bidirectional"))
    )
    (net (code "112") (name "unconnected-(IC2-PQ3-Pad88)") (class "Default")
      (node (ref "IC2") (pin "88") (pinfunction "PQ3_88") (pintype "bidirectional"))
    )
    (net (code "113") (name "unconnected-(MIRROR_IDX-Pad4)") (class "Default")
      (node (ref "MIRROR_IDX") (pin "4") (pinfunction "4_4") (pintype "passive"))
    )
    (net (code "114") (name "unconnected-(PDI_ATMEL-NC-Pad3)") (class "Default")
      (node (ref "PDI_ATMEL") (pin "3") (pinfunction "NC_3") (pintype "passive"))
    )
    (net (code "115") (name "unconnected-(PDI_ATMEL-NC.-Pad4)") (class "Default")
      (node (ref "PDI_ATMEL") (pin "4") (pinfunction "NC._4") (pintype "passive"))
    )
  )
)
